# Mega_Shield-v13.net
KiCad netlist of a schematic drawn in EAGLE
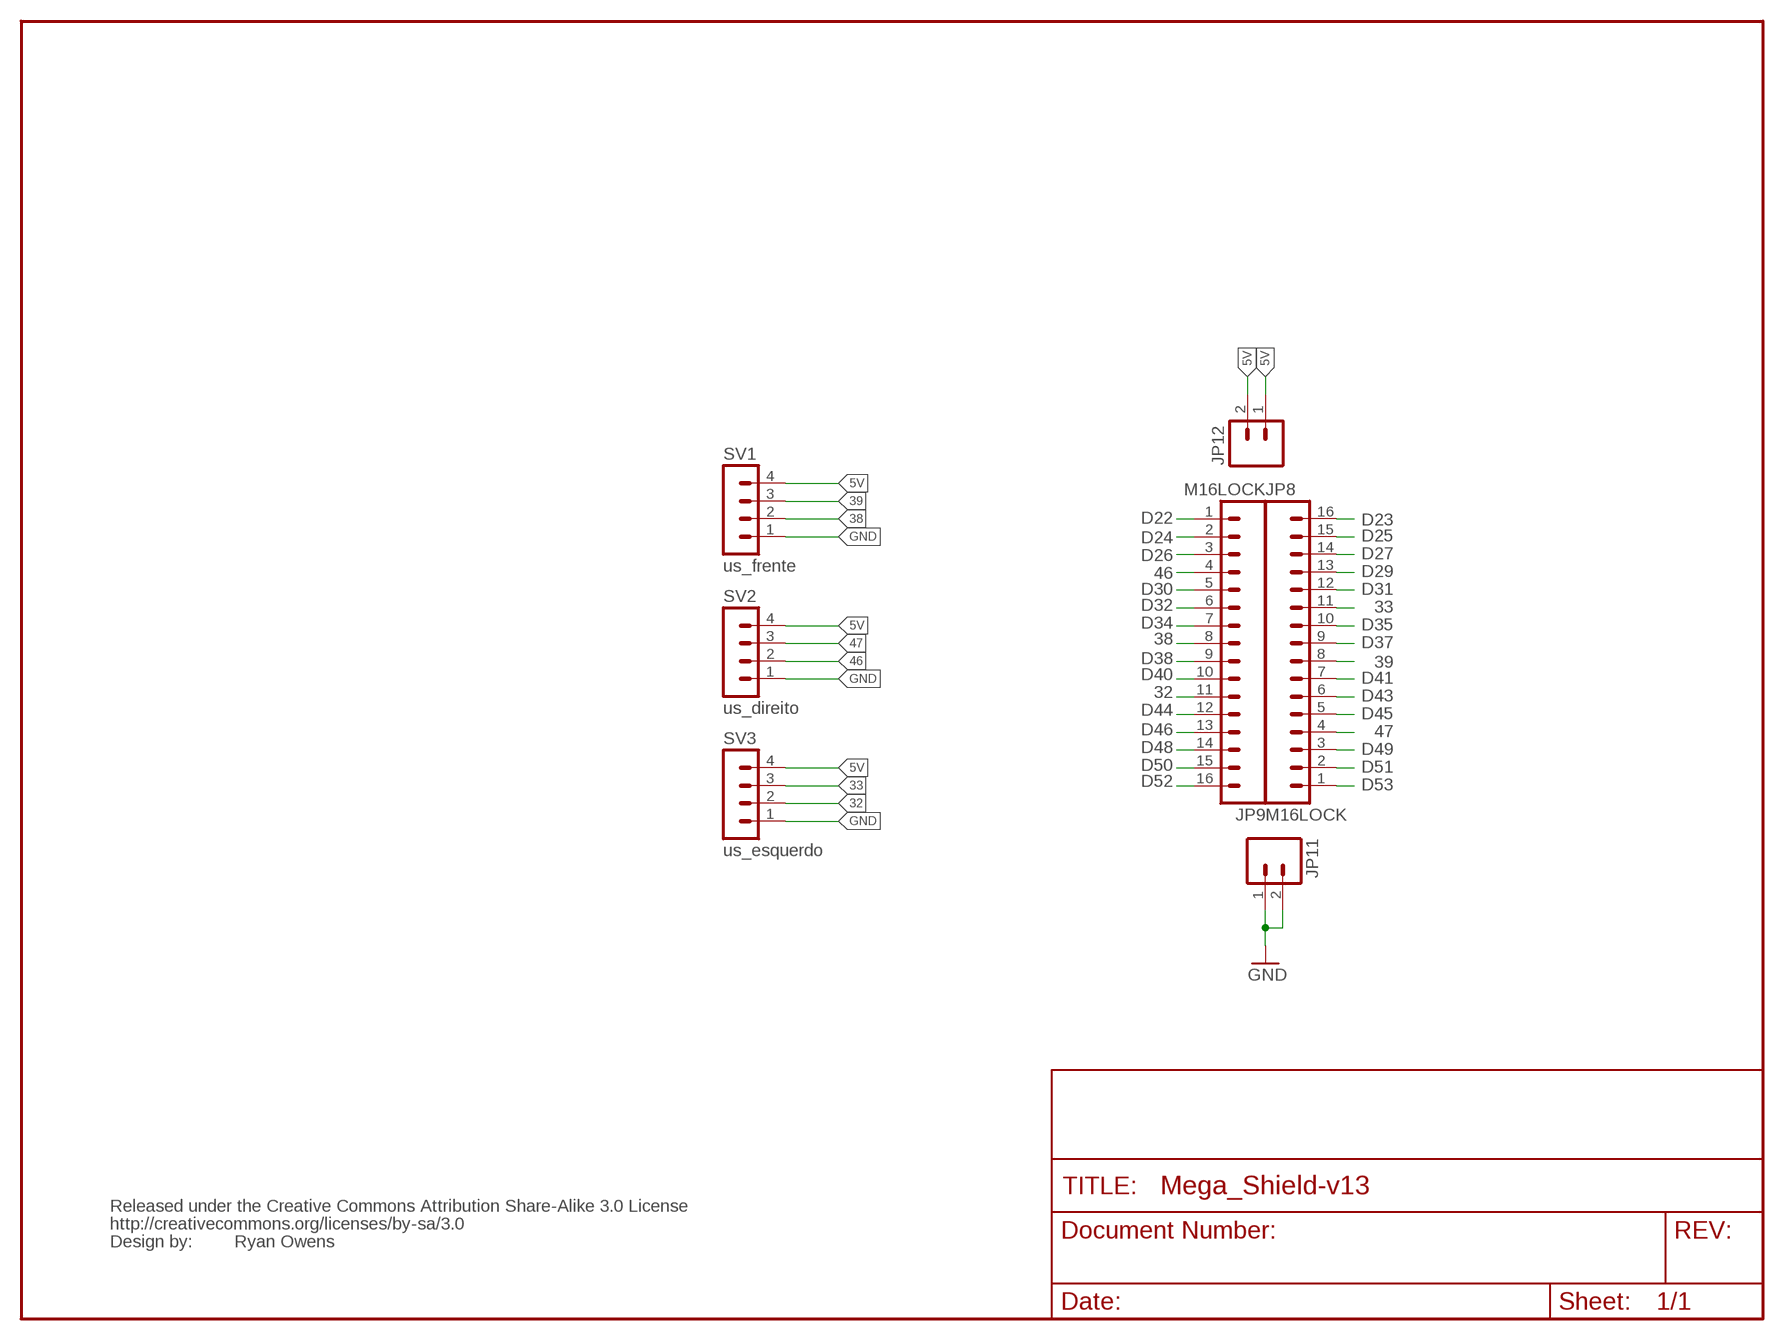
[diagram p0: schematic, sheet 1]

(export (version "E")
  (design (tool "Eeschema 10.0.6"))
  (components
    (comp (ref "JP8")
      (value "M16LOCK")
      (footprint "eagle-import:1X16_LOCK")
      (libsource (lib "eagle-import") (part "M16LOCK"))
    )
    (comp (ref "JP9")
      (value "M16LOCK")
      (footprint "eagle-import:1X16_LOCK")
      (libsource (lib "eagle-import") (part "M16LOCK"))
    )
    (comp (ref "JP11")
      (value "M02LOCK")
      (footprint "eagle-import:1X02_LOCK")
      (libsource (lib "eagle-import") (part "M02LOCK"))
    )
    (comp (ref "JP12")
      (value "M02LOCK")
      (footprint "eagle-import:1X02_LOCK")
      (libsource (lib "eagle-import") (part "M02LOCK"))
    )
    (comp (ref "SV1")
      (value "us_frente")
      (footprint "eagle-import:MA04-1")
      (libsource (lib "eagle-import") (part "MA04-1"))
    )
    (comp (ref "SV2")
      (value "us_direito")
      (footprint "eagle-import:MA04-1")
      (libsource (lib "eagle-import") (part "MA04-1"))
    )
    (comp (ref "SV3")
      (value "us_esquerdo")
      (footprint "eagle-import:MA04-1")
      (libsource (lib "eagle-import") (part "MA04-1"))
    )
    (comp (ref "U$2")
      (value "CREATIVE_COMMONS")
      (footprint "eagle-import:CREATIVE_COMMONS")
      (libsource (lib "eagle-import") (part "CREATIVE_COMMONS"))
    )
  )
  (nets
    (net (code "1") (name "/D22") (class "Default")
      (node (ref "JP9") (pin "1") (pinfunction "1_1") (pintype "passive"))
    )
    (net (code "2") (name "/D23") (class "Default")
      (node (ref "JP8") (pin "16") (pinfunction "16_16") (pintype "passive"))
    )
    (net (code "3") (name "/D24") (class "Default")
      (node (ref "JP9") (pin "2") (pinfunction "2_2") (pintype "passive"))
    )
    (net (code "4") (name "/D25") (class "Default")
      (node (ref "JP8") (pin "15") (pinfunction "15_15") (pintype "passive"))
    )
    (net (code "5") (name "/D26") (class "Default")
      (node (ref "JP9") (pin "3") (pinfunction "3_3") (pintype "passive"))
    )
    (net (code "6") (name "/D27") (class "Default")
      (node (ref "JP8") (pin "14") (pinfunction "14_14") (pintype "passive"))
    )
    (net (code "7") (name "/D29") (class "Default")
      (node (ref "JP8") (pin "13") (pinfunction "13_13") (pintype "passive"))
    )
    (net (code "8") (name "/D30") (class "Default")
      (node (ref "JP9") (pin "5") (pinfunction "5_5") (pintype "passive"))
    )
    (net (code "9") (name "/D31") (class "Default")
      (node (ref "JP8") (pin "12") (pinfunction "12_12") (pintype "passive"))
    )
    (net (code "10") (name "/D32") (class "Default")
      (node (ref "JP9") (pin "6") (pinfunction "6_6") (pintype "passive"))
    )
    (net (code "11") (name "/D34") (class "Default")
      (node (ref "JP9") (pin "7") (pinfunction "7_7") (pintype "passive"))
    )
    (net (code "12") (name "/D35") (class "Default")
      (node (ref "JP8") (pin "10") (pinfunction "10_10") (pintype "passive"))
    )
    (net (code "13") (name "/D37") (class "Default")
      (node (ref "JP8") (pin "9") (pinfunction "9_9") (pintype "passive"))
    )
    (net (code "14") (name "/D38") (class "Default")
      (node (ref "JP9") (pin "9") (pinfunction "9_9") (pintype "passive"))
    )
    (net (code "15") (name "/D40") (class "Default")
      (node (ref "JP9") (pin "10") (pinfunction "10_10") (pintype "passive"))
    )
    (net (code "16") (name "/D41") (class "Default")
      (node (ref "JP8") (pin "7") (pinfunction "7_7") (pintype "passive"))
    )
    (net (code "17") (name "/D43") (class "Default")
      (node (ref "JP8") (pin "6") (pinfunction "6_6") (pintype "passive"))
    )
    (net (code "18") (name "/D44") (class "Default")
      (node (ref "JP9") (pin "12") (pinfunction "12_12") (pintype "passive"))
    )
    (net (code "19") (name "/D45") (class "Default")
      (node (ref "JP8") (pin "5") (pinfunction "5_5") (pintype "passive"))
    )
    (net (code "20") (name "/D46") (class "Default")
      (node (ref "JP9") (pin "13") (pinfunction "13_13") (pintype "passive"))
    )
    (net (code "21") (name "/D48") (class "Default")
      (node (ref "JP9") (pin "14") (pinfunction "14_14") (pintype "passive"))
    )
    (net (code "22") (name "/D49") (class "Default")
      (node (ref "JP8") (pin "3") (pinfunction "3_3") (pintype "passive"))
    )
    (net (code "23") (name "/D50") (class "Default")
      (node (ref "JP9") (pin "15") (pinfunction "15_15") (pintype "passive"))
    )
    (net (code "24") (name "/D51") (class "Default")
      (node (ref "JP8") (pin "2") (pinfunction "2_2") (pintype "passive"))
    )
    (net (code "25") (name "/D52") (class "Default")
      (node (ref "JP9") (pin "16") (pinfunction "16_16") (pintype "passive"))
    )
    (net (code "26") (name "/D53") (class "Default")
      (node (ref "JP8") (pin "1") (pinfunction "1_1") (pintype "passive"))
    )
    (net (code "27") (name "5V") (class "Default")
      (node (ref "JP12") (pin "1") (pinfunction "1_1") (pintype "passive"))
      (node (ref "JP12") (pin "2") (pinfunction "2_2") (pintype "passive"))
      (node (ref "SV1") (pin "4") (pinfunction "4_4") (pintype "passive"))
      (node (ref "SV2") (pin "4") (pinfunction "4_4") (pintype "passive"))
      (node (ref "SV3") (pin "4") (pinfunction "4_4") (pintype "passive"))
    )
    (net (code "28") (name "32") (class "Default")
      (node (ref "JP9") (pin "11") (pinfunction "11_11") (pintype "passive"))
      (node (ref "SV3") (pin "2") (pinfunction "2_2") (pintype "passive"))
    )
    (net (code "29") (name "33") (class "Default")
      (node (ref "JP8") (pin "11") (pinfunction "11_11") (pintype "passive"))
      (node (ref "SV3") (pin "3") (pinfunction "3_3") (pintype "passive"))
    )
    (net (code "30") (name "38") (class "Default")
      (node (ref "JP9") (pin "8") (pinfunction "8_8") (pintype "passive"))
      (node (ref "SV1") (pin "2") (pinfunction "2_2") (pintype "passive"))
    )
    (net (code "31") (name "39") (class "Default")
      (node (ref "JP8") (pin "8") (pinfunction "8_8") (pintype "passive"))
      (node (ref "SV1") (pin "3") (pinfunction "3_3") (pintype "passive"))
    )
    (net (code "32") (name "46") (class "Default")
      (node (ref "JP9") (pin "4") (pinfunction "4_4") (pintype "passive"))
      (node (ref "SV2") (pin "2") (pinfunction "2_2") (pintype "passive"))
    )
    (net (code "33") (name "47") (class "Default")
      (node (ref "JP8") (pin "4") (pinfunction "4_4") (pintype "passive"))
      (node (ref "SV2") (pin "3") (pinfunction "3_3") (pintype "passive"))
    )
    (net (code "34") (name "GND") (class "Default")
      (node (ref "JP11") (pin "1") (pinfunction "1_1") (pintype "passive"))
      (node (ref "JP11") (pin "2") (pinfunction "2_2") (pintype "passive"))
      (node (ref "SV1") (pin "1") (pinfunction "1_1") (pintype "passive"))
      (node (ref "SV2") (pin "1") (pinfunction "1_1") (pintype "passive"))
      (node (ref "SV3") (pin "1") (pinfunction "1_1") (pintype "passive"))
    )
  )
)
